# Pressure_ADC.net
KiCad netlist of a schematic drawn in Altium Designer
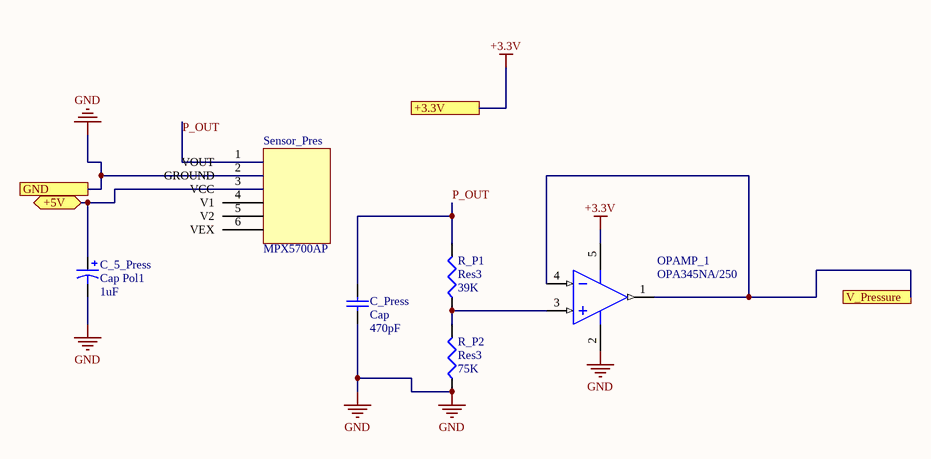
[diagram p0: Pressure ADC.SchDoc]

(export (version "E")
  (design (tool "Eeschema 10.0.6"))
  (components
    (comp (ref "C_5_Press")
      (value "Cap Pol1")
      (footprint "Capacitor S Panasonic")
      (description "Polarized Capacitor (Radial)")
      (fields (field (name "ALTIUM_VALUE") "1uF") (field (name "PUBLISHER") "Altium Limited"))
      (libsource (lib "Miscellaneous Devices") (part "Cap Pol1"))
    )
    (comp (ref "C_Press")
      (value "Cap")
      (footprint "J1-0603")
      (description "Capacitor")
      (fields (field (name "ALTIUM_VALUE") "470pF") (field (name "PUBLISHER") "Altium Limited"))
      (libsource (lib "Miscellaneous Devices") (part "Cap"))
    )
    (comp (ref "OPAMP_1")
      (value "OPA345NA/250")
      (footprint "TI-DBV5_N")
      (fields (field (name "MANUFACTURER") "Texas Instruments"))
      (libsource (lib "TI Amplifiers and Linear Operational Amplifier Precision Amplifier Part One") (part "OPA345NA/250"))
    )
    (comp (ref "R_P1")
      (value "Res3")
      (footprint "J1-0603")
      (description "Resistor")
      (fields (field (name "ALTIUM_VALUE") "39K") (field (name "PUBLISHER") "Altium Limited"))
      (libsource (lib "Miscellaneous Devices") (part "Res3"))
    )
    (comp (ref "R_P2")
      (value "Res3")
      (footprint "J1-0603")
      (description "Resistor")
      (fields (field (name "ALTIUM_VALUE") "75K") (field (name "PUBLISHER") "Altium Limited"))
      (libsource (lib "Miscellaneous Devices") (part "Res3"))
    )
    (comp (ref "Sensor_Pres")
      (value "MPX5700AP")
      (footprint "HDR1X6H")
      (libsource (lib "XSUB_COMP") (part "MPX5700AP"))
    )
  )
  (nets
    (net (code "1") (name "+3.3V") (class "Default")
      (node (ref "OPAMP_1") (pin "5") (pinfunction "V+_5") (pintype "power_in"))
    )
    (net (code "2") (name "/+5V") (class "Default")
      (node (ref "C_5_Press") (pin "1") (pinfunction "1_1") (pintype "passive"))
      (node (ref "Sensor_Pres") (pin "3") (pinfunction "VCC_3") (pintype "passive"))
    )
    (net (code "3") (name "/P_OUT") (class "Default")
      (node (ref "C_Press") (pin "2") (pinfunction "2_2") (pintype "passive"))
      (node (ref "R_P1") (pin "2") (pinfunction "2_2") (pintype "passive"))
      (node (ref "Sensor_Pres") (pin "1") (pinfunction "VOUT_1") (pintype "passive"))
    )
    (net (code "4") (name "/V_Pressure") (class "Default")
      (node (ref "OPAMP_1") (pin "1") (pinfunction "OUT_1") (pintype "output"))
      (node (ref "OPAMP_1") (pin "4") (pinfunction "IN-_4") (pintype "input"))
    )
    (net (code "5") (name "GND") (class "Default")
      (node (ref "C_5_Press") (pin "2") (pinfunction "2_2") (pintype "passive"))
      (node (ref "C_Press") (pin "1") (pinfunction "1_1") (pintype "passive"))
      (node (ref "OPAMP_1") (pin "2") (pinfunction "V-_2") (pintype "power_in"))
      (node (ref "R_P2") (pin "1") (pinfunction "1_1") (pintype "passive"))
      (node (ref "Sensor_Pres") (pin "2") (pinfunction "GROUND_2") (pintype "passive"))
    )
    (net (code "6") (name "Net-(OPAMP_1-IN+)") (class "Default")
      (node (ref "OPAMP_1") (pin "3") (pinfunction "IN+_3") (pintype "input"))
      (node (ref "R_P1") (pin "1") (pinfunction "1_1") (pintype "passive"))
      (node (ref "R_P2") (pin "2") (pinfunction "2_2") (pintype "passive"))
    )
    (net (code "7") (name "unconnected-(Sensor_Pres-V1-Pad4)") (class "Default")
      (node (ref "Sensor_Pres") (pin "4") (pinfunction "V1_4") (pintype "passive"))
    )
    (net (code "8") (name "unconnected-(Sensor_Pres-V2-Pad5)") (class "Default")
      (node (ref "Sensor_Pres") (pin "5") (pinfunction "V2_5") (pintype "passive"))
    )
    (net (code "9") (name "unconnected-(Sensor_Pres-VEX-Pad6)") (class "Default")
      (node (ref "Sensor_Pres") (pin "6") (pinfunction "VEX_6") (pintype "passive"))
    )
  )
)
